# 3-MCU.net
KiCad netlist of a schematic drawn in Altium Designer
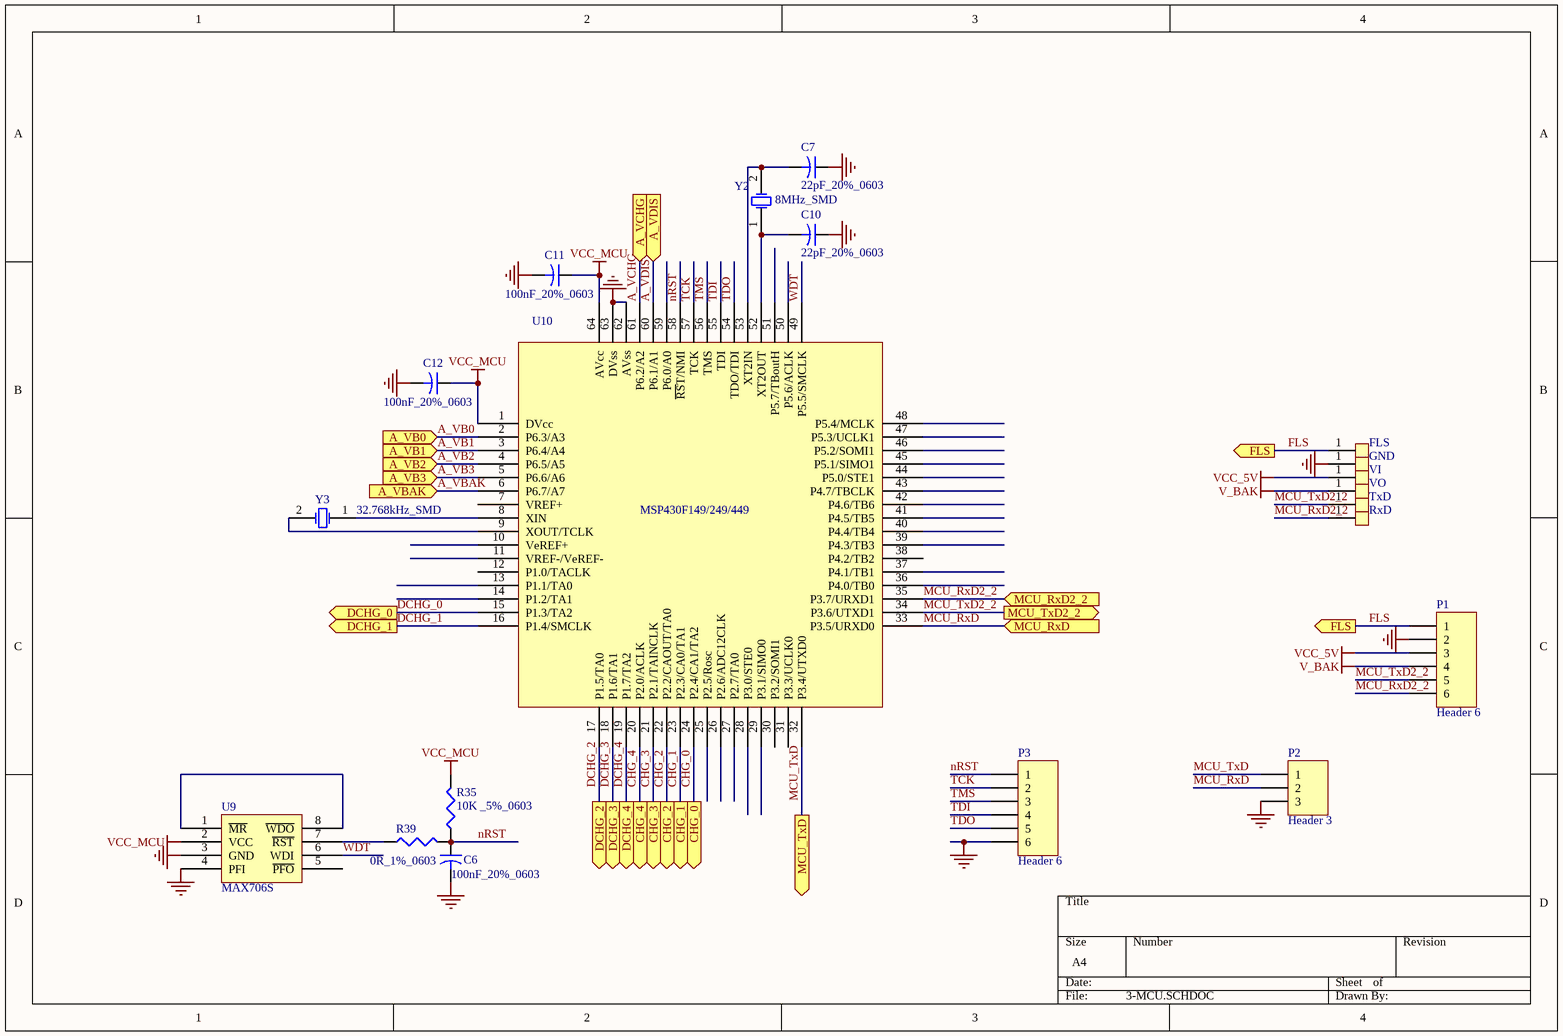
[diagram p0: 3-MCU.SCHDOC]

(export (version "E")
  (design (tool "Eeschema 10.0.6"))
  (components
    (comp (ref "C6")
      (value "100nF_20%_0603")
      (footprint "C1608-0603")
      (description "Capacitor")
      (fields (field (name "PUBLISHER") "Altium Limited"))
      (libsource (lib "Miscellaneous Devices") (part "Cap2"))
    )
    (comp (ref "C7")
      (value "22pF_20%_0603")
      (footprint "C1608-0603")
      (description "Capacitor")
      (fields (field (name "PUBLISHER") "Altium Limited"))
      (libsource (lib "Miscellaneous Devices") (part "Cap2"))
    )
    (comp (ref "C10")
      (value "22pF_20%_0603")
      (footprint "C1608-0603")
      (description "Capacitor")
      (fields (field (name "PUBLISHER") "Altium Limited"))
      (libsource (lib "Miscellaneous Devices") (part "Cap2"))
    )
    (comp (ref "C11")
      (value "100nF_20%_0603")
      (footprint "C1608-0603")
      (description "Capacitor")
      (fields (field (name "PUBLISHER") "Altium Limited"))
      (libsource (lib "Miscellaneous Devices") (part "Cap2"))
    )
    (comp (ref "C12")
      (value "100nF_20%_0603")
      (footprint "C1608-0603")
      (description "Capacitor")
      (fields (field (name "PUBLISHER") "Altium Limited"))
      (libsource (lib "Miscellaneous Devices") (part "Cap2"))
    )
    (comp (ref "FLS") (value "ND") (footprint "END_1.5_2.8") (libsource (lib "Device") (part "ND")))
    (comp (ref "GND") (value "ND") (footprint "END_1.5_2.8") (libsource (lib "Device") (part "ND")))
    (comp (ref "P1")
      (value "Header 6")
      (footprint "XH-06H")
      (description "Header, 6-Pin")
      (fields (field (name "PUBLISHER") "Altium Limited"))
      (libsource (lib "Miscellaneous Connectors") (part "Header 6"))
    )
    (comp (ref "P2")
      (value "Header 3")
      (footprint "XH-03H")
      (description "Header, 3-Pin")
      (fields (field (name "PUBLISHER") "Altium Limited"))
      (libsource (lib "Miscellaneous Connectors") (part "Header 3"))
    )
    (comp (ref "P3")
      (value "Header 6")
      (footprint "SH-06S")
      (description "Header, 6-Pin")
      (fields (field (name "PUBLISHER") "Altium Limited"))
      (libsource (lib "Miscellaneous Connectors") (part "Header 6"))
    )
    (comp (ref "R35")
      (value "10K _5%_0603")
      (footprint "C1608-0603")
      (description "Resistor")
      (fields (field (name "PUBLISHER") "Altium Limited"))
      (libsource (lib "Miscellaneous Devices") (part "Res3"))
    )
    (comp (ref "R39")
      (value "0R_1%_0603")
      (footprint "C1608-0603")
      (description "Resistor")
      (fields (field (name "PUBLISHER") "Altium Limited"))
      (libsource (lib "Miscellaneous Devices") (part "Res3"))
    )
    (comp (ref "RxD") (value "ND") (footprint "END_1.5_2.8") (libsource (lib "Device") (part "ND")))
    (comp (ref "TxD") (value "ND") (footprint "END_1.5_2.8") (libsource (lib "Device") (part "ND")))
    (comp (ref "U9") (value "MAX706S") (footprint "SO-8") (libsource (lib "Device") (part "MAX706")))
    (comp (ref "U10")
      (value "MSP430F149/249/449")
      (footprint "QFP-64")
      (libsource (lib "Device") (part "MSP430F149/249/449"))
    )
    (comp (ref "VI") (value "ND") (footprint "END_1.5_2.8") (libsource (lib "Device") (part "ND")))
    (comp (ref "VO") (value "ND") (footprint "END_1.5_2.8") (libsource (lib "Device") (part "ND")))
    (comp (ref "Y2")
      (value "8MHz_SMD")
      (footprint "XTAL-P4mm_SMD")
      (description "Crystal Oscillator")
      (fields (field (name "PUBLISHER") "Altium Limited"))
      (libsource (lib "Miscellaneous Devices") (part "XTAL"))
    )
    (comp (ref "Y3")
      (value "32.768kHz_SMD")
      (footprint "XTAL-3216")
      (description "Crystal Oscillator")
      (fields (field (name "PUBLISHER") "Altium Limited"))
      (libsource (lib "Miscellaneous Devices") (part "XTAL"))
    )
  )
  (nets
    (net (code "1") (name "/A_VB0") (class "Default")
      (node (ref "U10") (pin "2") (pinfunction "P6.3/A3_2") (pintype "power_in"))
    )
    (net (code "2") (name "/A_VB1") (class "Default")
      (node (ref "U10") (pin "3") (pinfunction "P6.4/A4_3") (pintype "power_in"))
    )
    (net (code "3") (name "/A_VB2") (class "Default")
      (node (ref "U10") (pin "4") (pinfunction "P6.5/A5_4") (pintype "power_in"))
    )
    (net (code "4") (name "/A_VB3") (class "Default")
      (node (ref "U10") (pin "5") (pinfunction "P6.6/A6_5") (pintype "power_in"))
    )
    (net (code "5") (name "/A_VBAK") (class "Default")
      (node (ref "U10") (pin "6") (pinfunction "P6.7/A7_6") (pintype "power_in"))
    )
    (net (code "6") (name "/A_VCHG") (class "Default")
      (node (ref "U10") (pin "61") (pinfunction "P6.2/A2_61") (pintype "power_in"))
    )
    (net (code "7") (name "/A_VDIS") (class "Default")
      (node (ref "U10") (pin "60") (pinfunction "P6.1/A1_60") (pintype "power_in"))
    )
    (net (code "8") (name "/CHG_0") (class "Default")
      (node (ref "U10") (pin "24") (pinfunction "P2.4/CA1/TA2_24") (pintype "power_in"))
    )
    (net (code "9") (name "/CHG_1") (class "Default")
      (node (ref "U10") (pin "23") (pinfunction "P2.3/CA0/TA1_23") (pintype "power_in"))
    )
    (net (code "10") (name "/CHG_2") (class "Default")
      (node (ref "U10") (pin "22") (pinfunction "P2.2/CAOUT/TA0_22") (pintype "power_in"))
    )
    (net (code "11") (name "/CHG_3") (class "Default")
      (node (ref "U10") (pin "21") (pinfunction "P2.1/TAINCLK_21") (pintype "power_in"))
    )
    (net (code "12") (name "/CHG_4") (class "Default")
      (node (ref "U10") (pin "20") (pinfunction "P2.0/ACLK_20") (pintype "power_in"))
    )
    (net (code "13") (name "/DCHG_0") (class "Default")
      (node (ref "U10") (pin "15") (pinfunction "P1.3/TA2_15") (pintype "power_in"))
    )
    (net (code "14") (name "/DCHG_1") (class "Default")
      (node (ref "U10") (pin "16") (pinfunction "P1.4/SMCLK_16") (pintype "power_in"))
    )
    (net (code "15") (name "/DCHG_2") (class "Default")
      (node (ref "U10") (pin "17") (pinfunction "P1.5/TA0_17") (pintype "power_in"))
    )
    (net (code "16") (name "/DCHG_3") (class "Default")
      (node (ref "U10") (pin "18") (pinfunction "P1.6/TA1_18") (pintype "power_in"))
    )
    (net (code "17") (name "/DCHG_4") (class "Default")
      (node (ref "U10") (pin "19") (pinfunction "P1.7/TA2_19") (pintype "power_in"))
    )
    (net (code "18") (name "/FLS") (class "Default")
      (node (ref "FLS") (pin "1") (pinfunction "SW_1") (pintype "passive"))
      (node (ref "P1") (pin "1") (pinfunction "1_1") (pintype "passive"))
    )
    (net (code "19") (name "/MCU_RxD") (class "Default")
      (node (ref "P2") (pin "2") (pinfunction "2_2") (pintype "passive"))
      (node (ref "U10") (pin "33") (pinfunction "P3.5/URXD0_33") (pintype "power_in"))
    )
    (net (code "20") (name "/MCU_RxD2_2") (class "Default")
      (node (ref "P1") (pin "6") (pinfunction "6_6") (pintype "passive"))
      (node (ref "RxD") (pin "1") (pinfunction "SW_1") (pintype "passive"))
      (node (ref "U10") (pin "35") (pinfunction "P3.7/URXD1_35") (pintype "power_in"))
    )
    (net (code "21") (name "/MCU_TxD") (class "Default")
      (node (ref "P2") (pin "1") (pinfunction "1_1") (pintype "passive"))
      (node (ref "U10") (pin "32") (pinfunction "P3.4/UTXD0_32") (pintype "power_in"))
    )
    (net (code "22") (name "/MCU_TxD2_2") (class "Default")
      (node (ref "P1") (pin "5") (pinfunction "5_5") (pintype "passive"))
      (node (ref "TxD") (pin "1") (pinfunction "SW_1") (pintype "passive"))
      (node (ref "U10") (pin "34") (pinfunction "P3.6/UTXD1_34") (pintype "power_in"))
    )
    (net (code "23") (name "/TCK") (class "Default")
      (node (ref "P3") (pin "2") (pinfunction "2_2") (pintype "passive"))
      (node (ref "U10") (pin "57") (pinfunction "TCK_57") (pintype "power_in"))
    )
    (net (code "24") (name "/TDI") (class "Default")
      (node (ref "P3") (pin "4") (pinfunction "4_4") (pintype "passive"))
      (node (ref "U10") (pin "55") (pinfunction "TDI_55") (pintype "power_in"))
    )
    (net (code "25") (name "/TDO") (class "Default")
      (node (ref "P3") (pin "5") (pinfunction "5_5") (pintype "passive"))
      (node (ref "U10") (pin "54") (pinfunction "TDO/TDI_54") (pintype "power_in"))
    )
    (net (code "26") (name "/TMS") (class "Default")
      (node (ref "P3") (pin "3") (pinfunction "3_3") (pintype "passive"))
      (node (ref "U10") (pin "56") (pinfunction "TMS_56") (pintype "power_in"))
    )
    (net (code "27") (name "/WDT") (class "Default")
      (node (ref "U10") (pin "49") (pinfunction "P5.5/SMCLK_49") (pintype "power_in"))
      (node (ref "U9") (pin "6") (pinfunction "WDI_6") (pintype "passive"))
    )
    (net (code "28") (name "/nRST") (class "Default")
      (node (ref "C6") (pin "1") (pinfunction "1_1") (pintype "passive"))
      (node (ref "P3") (pin "1") (pinfunction "1_1") (pintype "passive"))
      (node (ref "R35") (pin "1") (pinfunction "1_1") (pintype "passive"))
      (node (ref "R39") (pin "2") (pinfunction "2_2") (pintype "passive"))
      (node (ref "U10") (pin "58") (pinfunction "~{RS}T/NMI_58") (pintype "power_in"))
    )
    (net (code "29") (name "GND") (class "Default")
      (node (ref "C10") (pin "1") (pinfunction "1_1") (pintype "passive"))
      (node (ref "C11") (pin "2") (pinfunction "2_2") (pintype "passive"))
      (node (ref "C12") (pin "2") (pinfunction "2_2") (pintype "passive"))
      (node (ref "C6") (pin "2") (pinfunction "2_2") (pintype "passive"))
      (node (ref "C7") (pin "1") (pinfunction "1_1") (pintype "passive"))
      (node (ref "GND") (pin "1") (pinfunction "SW_1") (pintype "passive"))
      (node (ref "P1") (pin "2") (pinfunction "2_2") (pintype "passive"))
      (node (ref "P2") (pin "3") (pinfunction "3_3") (pintype "passive"))
      (node (ref "P3") (pin "6") (pinfunction "6_6") (pintype "passive"))
      (node (ref "U10") (pin "62") (pinfunction "AVss_62") (pintype "power_in"))
      (node (ref "U10") (pin "63") (pinfunction "DVss_63") (pintype "power_in"))
      (node (ref "U9") (pin "3") (pinfunction "GND_3") (pintype "passive"))
      (node (ref "U9") (pin "4") (pinfunction "PFI_4") (pintype "passive"))
    )
    (net (code "30") (name "Net-(U9-~{MR})") (class "Default")
      (node (ref "U9") (pin "1") (pinfunction "~{MR}_1") (pintype "passive"))
      (node (ref "U9") (pin "8") (pinfunction "~{WDO}_8") (pintype "passive"))
    )
    (net (code "31") (name "Net-(U9-~{RST})") (class "Default")
      (node (ref "R39") (pin "1") (pinfunction "1_1") (pintype "passive"))
      (node (ref "U9") (pin "7") (pinfunction "~{RST}_7") (pintype "passive"))
    )
    (net (code "32") (name "Net-(U10-XIN)") (class "Default")
      (node (ref "U10") (pin "8") (pinfunction "XIN_8") (pintype "power_in"))
      (node (ref "Y3") (pin "1") (pinfunction "OSC1_1") (pintype "passive"))
    )
    (net (code "33") (name "Net-(U10-XOUT{slash}TCLK)") (class "Default")
      (node (ref "U10") (pin "9") (pinfunction "XOUT/TCLK_9") (pintype "power_in"))
      (node (ref "Y3") (pin "2") (pinfunction "OSC2_2") (pintype "passive"))
    )
    (net (code "34") (name "Net-(U10-XT2IN)") (class "Default")
      (node (ref "C7") (pin "2") (pinfunction "2_2") (pintype "passive"))
      (node (ref "U10") (pin "53") (pinfunction "XT2IN_53") (pintype "power_in"))
      (node (ref "Y2") (pin "2") (pinfunction "OSC2_2") (pintype "passive"))
    )
    (net (code "35") (name "Net-(U10-XT2OUT)") (class "Default")
      (node (ref "C10") (pin "2") (pinfunction "2_2") (pintype "passive"))
      (node (ref "U10") (pin "52") (pinfunction "XT2OUT_52") (pintype "power_in"))
      (node (ref "Y2") (pin "1") (pinfunction "OSC1_1") (pintype "passive"))
    )
    (net (code "36") (name "VCC_5V") (class "Default")
      (node (ref "P1") (pin "3") (pinfunction "3_3") (pintype "passive"))
      (node (ref "VI") (pin "1") (pinfunction "SW_1") (pintype "passive"))
    )
    (net (code "37") (name "VCC_MCU") (class "Default")
      (node (ref "C11") (pin "1") (pinfunction "1_1") (pintype "passive"))
      (node (ref "C12") (pin "1") (pinfunction "1_1") (pintype "passive"))
      (node (ref "R35") (pin "2") (pinfunction "2_2") (pintype "passive"))
      (node (ref "U10") (pin "1") (pinfunction "DVcc_1") (pintype "power_in"))
      (node (ref "U10") (pin "64") (pinfunction "AVcc_64") (pintype "power_in"))
      (node (ref "U9") (pin "2") (pinfunction "VCC_2") (pintype "passive"))
    )
    (net (code "38") (name "V_BAK") (class "Default")
      (node (ref "P1") (pin "4") (pinfunction "4_4") (pintype "passive"))
      (node (ref "VO") (pin "1") (pinfunction "SW_1") (pintype "passive"))
    )
    (net (code "39") (name "unconnected-(U9-~{PFO}-Pad5)") (class "Default")
      (node (ref "U9") (pin "5") (pinfunction "~{PFO}_5") (pintype "passive"))
    )
    (net (code "40") (name "unconnected-(U10-P1.0{slash}TACLK-Pad12)") (class "Default")
      (node (ref "U10") (pin "12") (pinfunction "P1.0/TACLK_12") (pintype "power_in"))
    )
    (net (code "41") (name "unconnected-(U10-P1.1{slash}TA0-Pad13)") (class "Default")
      (node (ref "U10") (pin "13") (pinfunction "P1.1/TA0_13") (pintype "power_in"))
    )
    (net (code "42") (name "unconnected-(U10-P1.2{slash}TA1-Pad14)") (class "Default")
      (node (ref "U10") (pin "14") (pinfunction "P1.2/TA1_14") (pintype "power_in"))
    )
    (net (code "43") (name "unconnected-(U10-P2.5{slash}Rosc-Pad25)") (class "Default")
      (node (ref "U10") (pin "25") (pinfunction "P2.5/Rosc_25") (pintype "power_in"))
    )
    (net (code "44") (name "unconnected-(U10-P2.6{slash}ADC12CLK-Pad26)") (class "Default")
      (node (ref "U10") (pin "26") (pinfunction "P2.6/ADC12CLK_26") (pintype "power_in"))
    )
    (net (code "45") (name "unconnected-(U10-P2.7{slash}TA0-Pad27)") (class "Default")
      (node (ref "U10") (pin "27") (pinfunction "P2.7/TA0_27") (pintype "power_in"))
    )
    (net (code "46") (name "unconnected-(U10-P3.0{slash}STE0-Pad28)") (class "Default")
      (node (ref "U10") (pin "28") (pinfunction "P3.0/STE0_28") (pintype "power_in"))
    )
    (net (code "47") (name "unconnected-(U10-P3.1{slash}SIMO0-Pad29)") (class "Default")
      (node (ref "U10") (pin "29") (pinfunction "P3.1/SIMO0_29") (pintype "power_in"))
    )
    (net (code "48") (name "unconnected-(U10-P3.2{slash}SOMI1-Pad30)") (class "Default")
      (node (ref "U10") (pin "30") (pinfunction "P3.2/SOMI1_30") (pintype "power_in"))
    )
    (net (code "49") (name "unconnected-(U10-P3.3{slash}UCLK0-Pad31)") (class "Default")
      (node (ref "U10") (pin "31") (pinfunction "P3.3/UCLK0_31") (pintype "power_in"))
    )
    (net (code "50") (name "unconnected-(U10-P4.0{slash}TB0-Pad36)") (class "Default")
      (node (ref "U10") (pin "36") (pinfunction "P4.0/TB0_36") (pintype "power_in"))
    )
    (net (code "51") (name "unconnected-(U10-P4.1{slash}TB1-Pad37)") (class "Default")
      (node (ref "U10") (pin "37") (pinfunction "P4.1/TB1_37") (pintype "power_in"))
    )
    (net (code "52") (name "unconnected-(U10-P4.2{slash}TB2-Pad38)") (class "Default")
      (node (ref "U10") (pin "38") (pinfunction "P4.2/TB2_38") (pintype "power_in"))
    )
    (net (code "53") (name "unconnected-(U10-P4.3{slash}TB3-Pad39)") (class "Default")
      (node (ref "U10") (pin "39") (pinfunction "P4.3/TB3_39") (pintype "power_in"))
    )
    (net (code "54") (name "unconnected-(U10-P4.4{slash}TB4-Pad40)") (class "Default")
      (node (ref "U10") (pin "40") (pinfunction "P4.4/TB4_40") (pintype "power_in"))
    )
    (net (code "55") (name "unconnected-(U10-P4.5{slash}TB5-Pad41)") (class "Default")
      (node (ref "U10") (pin "41") (pinfunction "P4.5/TB5_41") (pintype "power_in"))
    )
    (net (code "56") (name "unconnected-(U10-P4.6{slash}TB6-Pad42)") (class "Default")
      (node (ref "U10") (pin "42") (pinfunction "P4.6/TB6_42") (pintype "power_in"))
    )
    (net (code "57") (name "unconnected-(U10-P4.7{slash}TBCLK-Pad43)") (class "Default")
      (node (ref "U10") (pin "43") (pinfunction "P4.7/TBCLK_43") (pintype "power_in"))
    )
    (net (code "58") (name "unconnected-(U10-P5.0{slash}STE1-Pad44)") (class "Default")
      (node (ref "U10") (pin "44") (pinfunction "P5.0/STE1_44") (pintype "power_in"))
    )
    (net (code "59") (name "unconnected-(U10-P5.1{slash}SIMO1-Pad45)") (class "Default")
      (node (ref "U10") (pin "45") (pinfunction "P5.1/SIMO1_45") (pintype "power_in"))
    )
    (net (code "60") (name "unconnected-(U10-P5.2{slash}SOMI1-Pad46)") (class "Default")
      (node (ref "U10") (pin "46") (pinfunction "P5.2/SOMI1_46") (pintype "power_in"))
    )
    (net (code "61") (name "unconnected-(U10-P5.3{slash}UCLK1-Pad47)") (class "Default")
      (node (ref "U10") (pin "47") (pinfunction "P5.3/UCLK1_47") (pintype "power_in"))
    )
    (net (code "62") (name "unconnected-(U10-P5.4{slash}MCLK-Pad48)") (class "Default")
      (node (ref "U10") (pin "48") (pinfunction "P5.4/MCLK_48") (pintype "power_in"))
    )
    (net (code "63") (name "unconnected-(U10-P5.6{slash}ACLK-Pad50)") (class "Default")
      (node (ref "U10") (pin "50") (pinfunction "P5.6/ACLK_50") (pintype "power_in"))
    )
    (net (code "64") (name "unconnected-(U10-P5.7{slash}TBoutH-Pad51)") (class "Default")
      (node (ref "U10") (pin "51") (pinfunction "P5.7/TBoutH_51") (pintype "power_in"))
    )
    (net (code "65") (name "unconnected-(U10-P6.0{slash}A0-Pad59)") (class "Default")
      (node (ref "U10") (pin "59") (pinfunction "P6.0/A0_59") (pintype "power_in"))
    )
    (net (code "66") (name "unconnected-(U10-VREF+-Pad7)") (class "Default")
      (node (ref "U10") (pin "7") (pinfunction "VREF+_7") (pintype "power_in"))
    )
    (net (code "67") (name "unconnected-(U10-VREF-{slash}VeREF--Pad11)") (class "Default")
      (node (ref "U10") (pin "11") (pinfunction "VREF-/VeREF-_11") (pintype "power_in"))
    )
    (net (code "68") (name "unconnected-(U10-VeREF+-Pad10)") (class "Default")
      (node (ref "U10") (pin "10") (pinfunction "VeREF+_10") (pintype "power_in"))
    )
  )
)
